# 3_30.net
KiCad netlist of a schematic drawn in EasyEDA Pro
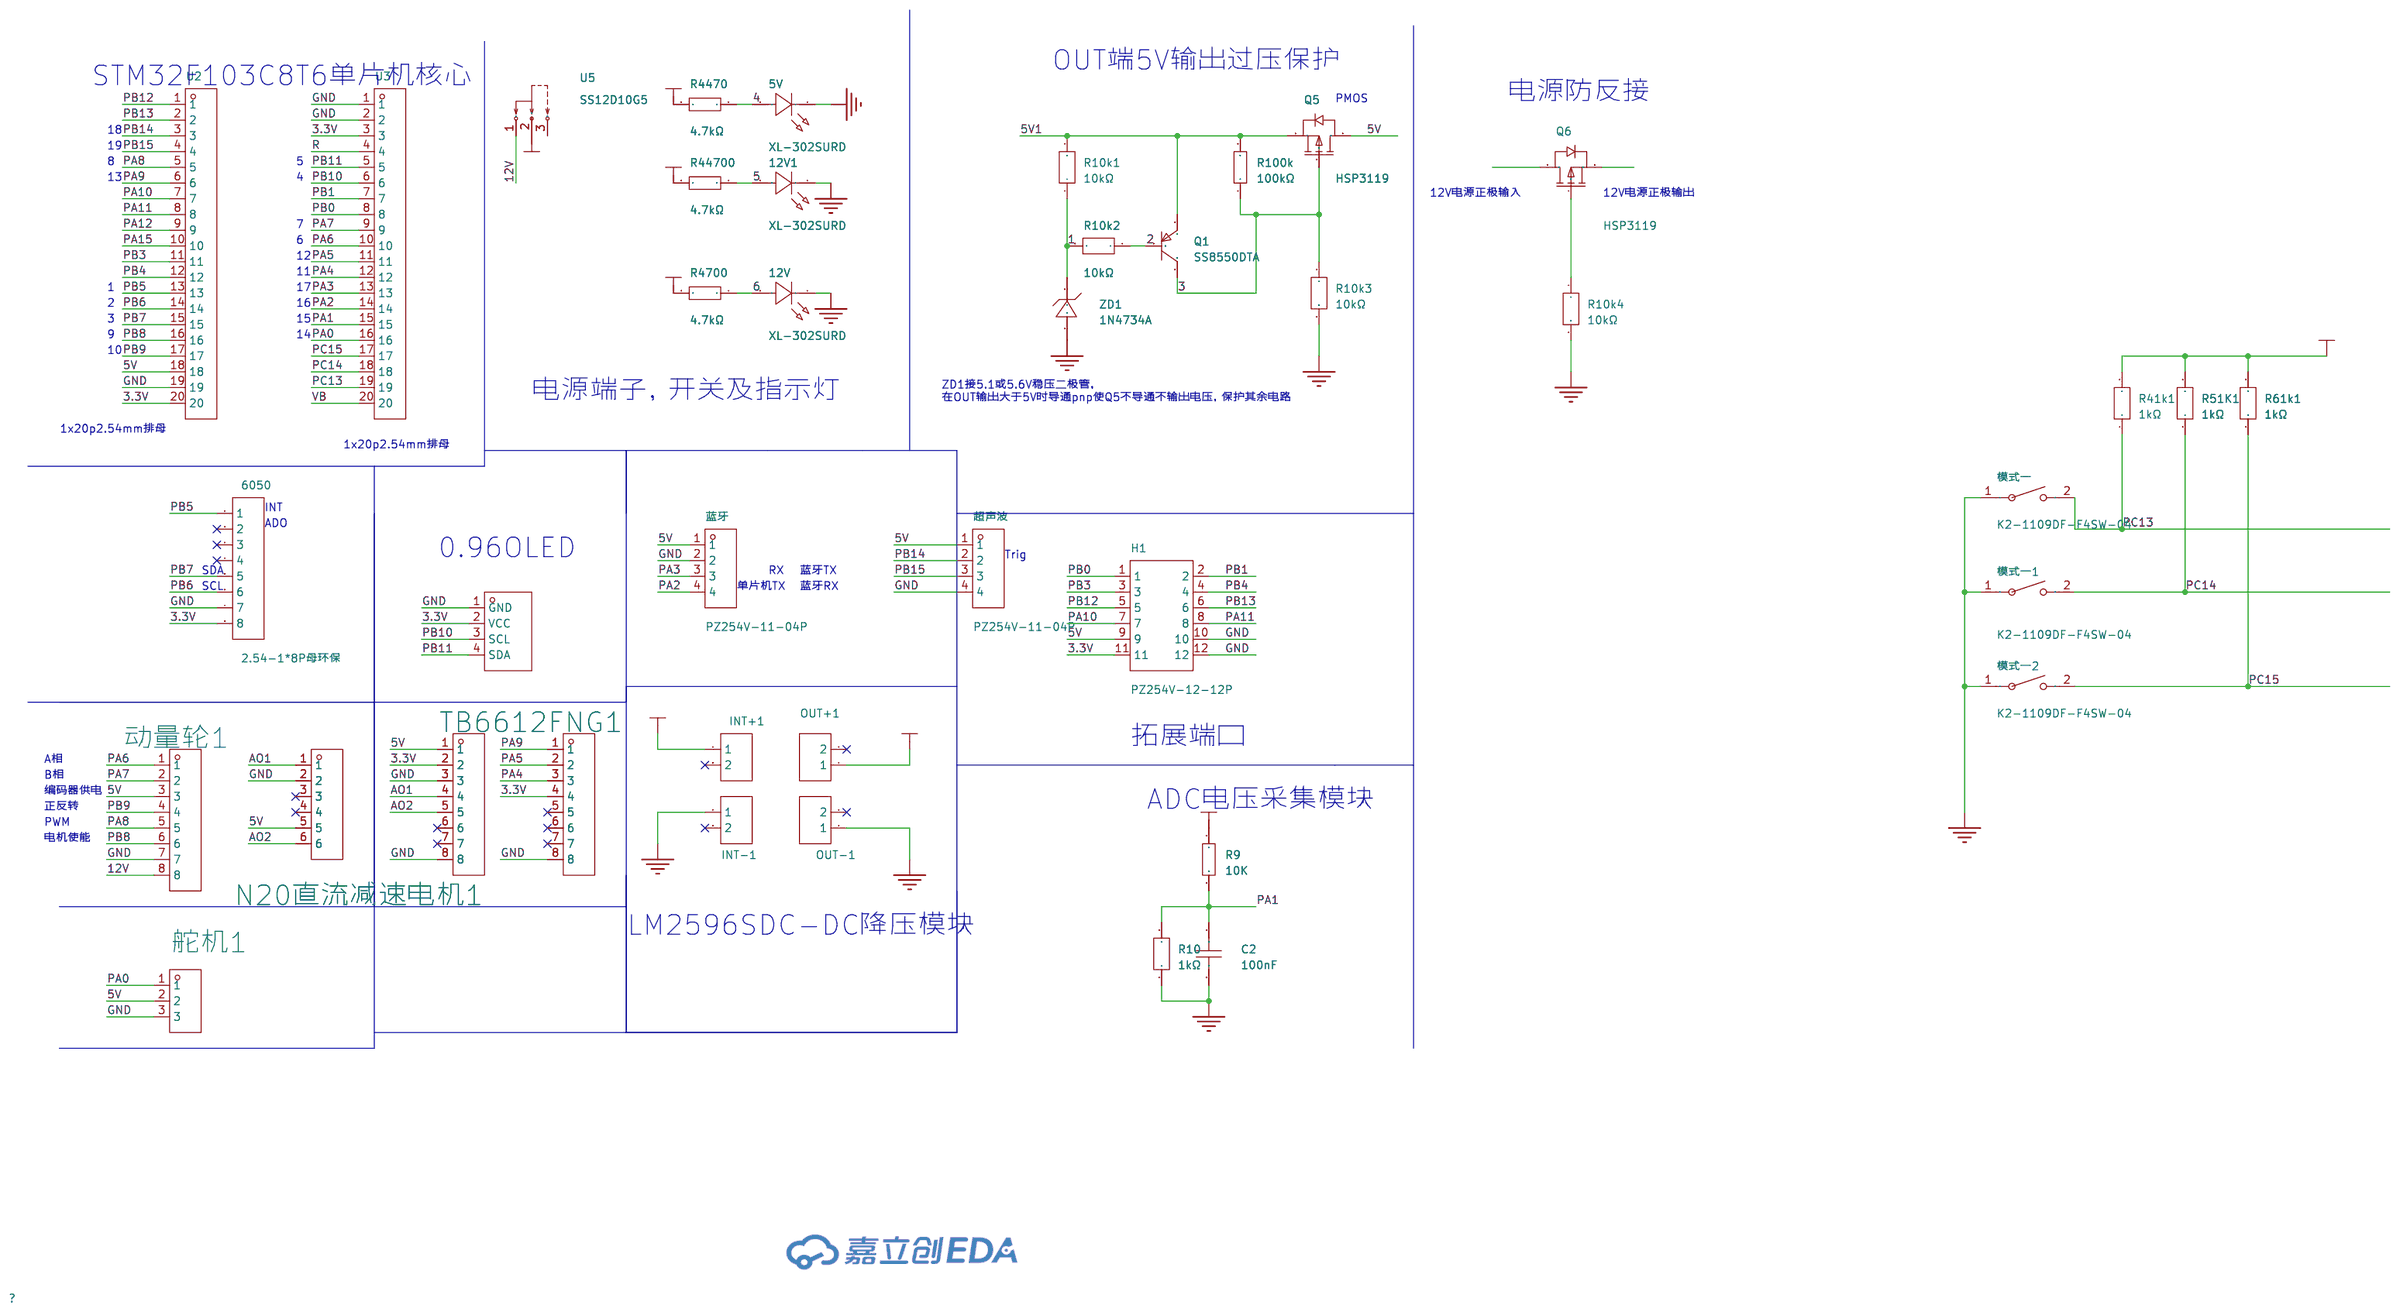
[diagram p0: schematic sheet]

(export (version "E")
  (design (tool "Eeschema 10.0.6"))
  (components
    (comp (ref "5V")
      (value "XL-302SURD")
      (footprint "easyedapro:LED-TH_BD3.8-P2.54-RD")
      (fields (field (name "Manufacturer") "XINGLIGHT(成兴光)"))
      (libsource (lib "easyedapro") (part "XL-302SURD"))
    )
    (comp (ref "12V")
      (value "XL-302SURD")
      (footprint "easyedapro:LED-TH_BD3.8-P2.54-RD")
      (fields (field (name "Manufacturer") "XINGLIGHT(成兴光)"))
      (libsource (lib "easyedapro") (part "XL-302SURD"))
    )
    (comp (ref "12V1")
      (value "XL-302SURD")
      (footprint "easyedapro:LED-TH_BD3.8-P2.54-RD")
      (fields (field (name "Manufacturer") "XINGLIGHT(成兴光)"))
      (libsource (lib "easyedapro") (part "XL-302SURD"))
    )
    (comp (ref "6050")
      (value "2.54-1*8P母环保")
      (footprint "easyedapro:HDR-TH_8P-P2.54-V-F-1")
      (description "插孔结构:1x8P;间距:2.54mm;行距:-;安装类型:直插;排数:单排;总孔位数:8P;塑高:-;触头材质:-;触头镀层:-;")
      (fields (field (name "Manufacturer") "BOOMELE(博穆精密)"))
      (libsource (lib "easyedapro") (part "Header-Female-2.54_1x8"))
    )
    (comp (ref "C2")
      (value "100nF")
      (footprint "easyedapro:C0603")
      (libsource (lib "easyedapro") (part "CapAcitance"))
    )
    (comp (ref "H1")
      (value "PZ254V-12-12P")
      (footprint "easyedapro:HDR-TH_12P-P2.54-V-M-R2-C6-S2.54")
      (fields (field (name "Manufacturer") "XFCN(兴飞)"))
      (libsource (lib "easyedapro") (part "PZ254V-12-12P"))
    )
    (comp (ref "INT+1")
      (value "2.54-1*2P母")
      (footprint "easyedapro:HDR-TH_2P-P2.54-V-F")
      (description "插孔结构:1x2P;间距:2.54mm;行距:-;安装类型:直插;排数:单排;总孔位数:2P;塑高:-;触头材质:-;触头镀层:-;")
      (fields (field (name "Manufacturer") "BOOMELE(博穆精密)"))
      (libsource (lib "easyedapro") (part "Header-Female-2.54_1x2"))
    )
    (comp (ref "INT-1")
      (value "2.54-1*2P母")
      (footprint "easyedapro:HDR-TH_2P-P2.54-V-F")
      (description "插孔结构:1x2P;间距:2.54mm;行距:-;安装类型:直插;排数:单排;总孔位数:2P;塑高:-;触头材质:-;触头镀层:-;")
      (fields (field (name "Manufacturer") "BOOMELE(博穆精密)"))
      (libsource (lib "easyedapro") (part "Header-Female-2.54_1x2"))
    )
    (comp (ref "N20直流减速电机1")
      (value "KH-2PH90-1X6P-L10.5")
      (footprint "easyedapro:HDR-TH_6P-P2.00-H-M-W7.2-N")
      (fields (field (name "Manufacturer") "kinghelm(金航标)"))
      (libsource (lib "easyedapro") (part "KH-2PH90-1X6P-L10.5"))
    )
    (comp (ref "OLED1")
      (value "HS96L03W2C03")
      (footprint "easyedapro:OLED-TH_L27.8-W27.2-P2.54_C9900033791")
      (description "主控芯片:SSD1315;接口类型:I2C;尺寸(inch):0.96;像素分辨率:128x64;")
      (fields (field (name "Manufacturer") "HS(汉昇)"))
      (libsource (lib "easyedapro") (part "HS96L03W2C03"))
    )
    (comp (ref "OUT+1")
      (value "2.54-1*2P母")
      (footprint "easyedapro:HDR-TH_2P-P2.54-V-F")
      (description "插孔结构:1x2P;间距:2.54mm;行距:-;安装类型:直插;排数:单排;总孔位数:2P;塑高:-;触头材质:-;触头镀层:-;")
      (fields (field (name "Manufacturer") "BOOMELE(博穆精密)"))
      (libsource (lib "easyedapro") (part "Header-Female-2.54_1x2"))
    )
    (comp (ref "OUT-1")
      (value "2.54-1*2P母")
      (footprint "easyedapro:HDR-TH_2P-P2.54-V-F")
      (description "插孔结构:1x2P;间距:2.54mm;行距:-;安装类型:直插;排数:单排;总孔位数:2P;塑高:-;触头材质:-;触头镀层:-;")
      (fields (field (name "Manufacturer") "BOOMELE(博穆精密)"))
      (libsource (lib "easyedapro") (part "Header-Female-2.54_1x2"))
    )
    (comp (ref "Q1")
      (value "SS8550DTA")
      (footprint "easyedapro:TO-92-3_L4.8-W3.7-P2.54-L")
      (description "晶体管类型:PNP;集电极电流(Ic):1.5A;集射极击穿电压(Vceo):25V;功率(Pd):2W;直流电流增益(hFE@Ic,Vce):40@800mA,1V;")
      (fields (field (name "Manufacturer") "onsemi(安森美)"))
      (libsource (lib "easyedapro") (part "SS8550DTA"))
    )
    (comp (ref "Q5")
      (value "HSP3119")
      (footprint "easyedapro:TO-220-3_L10.2-W4.5-P2.54-L-1")
      (description "类型:1个P沟道;漏源电压(Vdss):30V;连续漏极电流(Id):150A;导通电阻(RDS(on)):-;耗散功率(Pd):200W;阈值电压(Vgs(th)):2.5V;")
      (fields (field (name "Manufacturer") "HUASHUO(华朔)"))
      (libsource (lib "easyedapro") (part "HSP3119"))
    )
    (comp (ref "Q6")
      (value "HSP3119")
      (footprint "easyedapro:TO-220-3_L10.2-W4.5-P2.54-L-1")
      (description "类型:1个P沟道;漏源电压(Vdss):30V;连续漏极电流(Id):150A;导通电阻(RDS(on)):-;耗散功率(Pd):200W;阈值电压(Vgs(th)):2.5V;")
      (fields (field (name "Manufacturer") "HUASHUO(华朔)"))
      (libsource (lib "easyedapro") (part "HSP3119"))
    )
    (comp (ref "R9") (value "10K") (footprint "easyedapro:R0603") (libsource (lib "easyedapro") (part "电阻")))
    (comp (ref "R10")
      (value "1kΩ")
      (footprint "easyedapro:RES-TH_BD2.3-L6.5-P10.50-D0.5")
      (description "电阻类型:金属膜电阻;阻值:1kΩ;精度:±1%;功率:250mW;温度系数:±200ppm/°C;")
      (fields (field (name "Manufacturer Part") "MF1/4W-1KΩ±1%T52") (field (name "Manufacturer") "华星机电"))
      (libsource (lib "easyedapro") (part "MF1/4W-1KΩ±1%T52"))
    )
    (comp (ref "R10k1")
      (value "10kΩ")
      (footprint "easyedapro:RES-TH_BD2.4-L6.3-P10.30-D0.6")
      (description "电阻类型:金属膜电阻;阻值:10kΩ;精度:±1%;功率:250mW;温度系数:±50ppm/°C;")
      (fields
        (field (name "Manufacturer Part") "RN1/4W10KFT/BA1")
        (field (name "Manufacturer") "Tyohm(幸亚电阻)")
      )
      (libsource (lib "easyedapro") (part "RN 1/4W 10K F T/B A1"))
    )
    (comp (ref "R10k2")
      (value "10kΩ")
      (footprint "easyedapro:RES-TH_BD2.4-L6.3-P10.30-D0.6")
      (description "电阻类型:金属膜电阻;阻值:10kΩ;精度:±1%;功率:250mW;温度系数:±50ppm/°C;")
      (fields
        (field (name "Manufacturer Part") "RN1/4W10KFT/BA1")
        (field (name "Manufacturer") "Tyohm(幸亚电阻)")
      )
      (libsource (lib "easyedapro") (part "RN 1/4W 10K F T/B A1"))
    )
    (comp (ref "R10k3")
      (value "10kΩ")
      (footprint "easyedapro:RES-TH_BD2.4-L6.3-P10.30-D0.6")
      (description "电阻类型:金属膜电阻;阻值:10kΩ;精度:±1%;功率:250mW;温度系数:±50ppm/°C;")
      (fields
        (field (name "Manufacturer Part") "RN1/4W10KFT/BA1")
        (field (name "Manufacturer") "Tyohm(幸亚电阻)")
      )
      (libsource (lib "easyedapro") (part "RN 1/4W 10K F T/B A1"))
    )
    (comp (ref "R10k4")
      (value "10kΩ")
      (footprint "easyedapro:RES-TH_BD2.4-L6.3-P10.30-D0.6")
      (description "电阻类型:金属膜电阻;阻值:10kΩ;精度:±1%;功率:250mW;温度系数:±50ppm/°C;")
      (fields
        (field (name "Manufacturer Part") "RN1/4W10KFT/BA1")
        (field (name "Manufacturer") "Tyohm(幸亚电阻)")
      )
      (libsource (lib "easyedapro") (part "RN 1/4W 10K F T/B A1"))
    )
    (comp (ref "R41k1")
      (value "1kΩ")
      (footprint "easyedapro:RES-TH_BD2.3-L6.5-P10.50-D0.5")
      (description "电阻类型:金属膜电阻;阻值:1kΩ;精度:±1%;功率:250mW;温度系数:±200ppm/°C;")
      (fields (field (name "Manufacturer Part") "MF1/4W-1KΩ±1%T52") (field (name "Manufacturer") "华星机电"))
      (libsource (lib "easyedapro") (part "MF1/4W-1KΩ±1%T52"))
    )
    (comp (ref "R51K1")
      (value "1kΩ")
      (footprint "easyedapro:RES-TH_BD2.3-L6.5-P10.50-D0.5")
      (description "电阻类型:金属膜电阻;阻值:1kΩ;精度:±1%;功率:250mW;温度系数:±200ppm/°C;")
      (fields (field (name "Manufacturer Part") "MF1/4W-1KΩ±1%T52") (field (name "Manufacturer") "华星机电"))
      (libsource (lib "easyedapro") (part "MF1/4W-1KΩ±1%T52"))
    )
    (comp (ref "R61k1")
      (value "1kΩ")
      (footprint "easyedapro:RES-TH_BD2.3-L6.5-P10.50-D0.5")
      (description "电阻类型:金属膜电阻;阻值:1kΩ;精度:±1%;功率:250mW;温度系数:±200ppm/°C;")
      (fields (field (name "Manufacturer Part") "MF1/4W-1KΩ±1%T52") (field (name "Manufacturer") "华星机电"))
      (libsource (lib "easyedapro") (part "MF1/4W-1KΩ±1%T52"))
    )
    (comp (ref "R100k")
      (value "100kΩ")
      (footprint "easyedapro:RES-TH_BD2.7-L6.2-P10.20-D0.4")
      (description "电阻类型:金属膜电阻;阻值:100kΩ;精度:±1%;功率:250mW;温度系数:±350ppm/°C;")
      (fields (field (name "Manufacturer Part") "MF1/4W-100K±1%-OT26") (field (name "Manufacturer") "VO(翔胜)"))
      (libsource (lib "easyedapro") (part "MF1/4W-100K±1%-OT26"))
    )
    (comp (ref "R4470")
      (value "4.7kΩ")
      (footprint "easyedapro:R0402")
      (description "电阻类型:厚膜电阻;阻值:4.7kΩ;精度:±1%;功率:62.5mW;最大工作电压:50V;温度系数:±100ppm/°C;")
      (fields
        (field (name "Manufacturer Part") "0402WGF4701TCE")
        (field (name "Manufacturer") "UNI-ROYAL(厚声)")
      )
      (libsource (lib "easyedapro") (part "0402WGF4701TCE"))
    )
    (comp (ref "R4700")
      (value "4.7kΩ")
      (footprint "easyedapro:R0402")
      (description "电阻类型:厚膜电阻;阻值:4.7kΩ;精度:±1%;功率:62.5mW;最大工作电压:50V;温度系数:±100ppm/°C;")
      (fields
        (field (name "Manufacturer Part") "0402WGF4701TCE")
        (field (name "Manufacturer") "UNI-ROYAL(厚声)")
      )
      (libsource (lib "easyedapro") (part "0402WGF4701TCE"))
    )
    (comp (ref "R44700")
      (value "4.7kΩ")
      (footprint "easyedapro:R0402")
      (description "电阻类型:厚膜电阻;阻值:4.7kΩ;精度:±1%;功率:62.5mW;最大工作电压:50V;温度系数:±100ppm/°C;")
      (fields
        (field (name "Manufacturer Part") "0402WGF4701TCE")
        (field (name "Manufacturer") "UNI-ROYAL(厚声)")
      )
      (libsource (lib "easyedapro") (part "0402WGF4701TCE"))
    )
    (comp (ref "TB1")
      (value "2.54-1*8P/30mm(3+24+3)")
      (footprint "easyedapro:HDR-TH_8P-P2.54-V-M-4")
      (libsource (lib "easyedapro") (part "2.54-1*8P/30MM(3+24+3)"))
    )
    (comp (ref "TB6612FNG1")
      (value "2.54-1*8P/30mm(3+24+3)")
      (footprint "easyedapro:HDR-TH_8P-P2.54-V-M-4")
      (libsource (lib "easyedapro") (part "2.54-1*8P/30MM(3+24+3)"))
    )
    (comp (ref "U2")
      (value "KH-2FH-1X20P-H4.3")
      (footprint "easyedapro:HDR-TH_20P-P2.00-V-F-A")
      (fields (field (name "Manufacturer") "kinghelm(金航标)"))
      (libsource (lib "easyedapro") (part "KH-2FH-1X20P-H4.3"))
    )
    (comp (ref "U3")
      (value "KH-2FH-1X20P-H4.3")
      (footprint "easyedapro:HDR-TH_20P-P2.00-V-F-A")
      (fields (field (name "Manufacturer") "kinghelm(金航标)"))
      (libsource (lib "easyedapro") (part "KH-2FH-1X20P-H4.3"))
    )
    (comp (ref "U5")
      (value "SS12D10G5")
      (footprint "easyedapro:SW-TH_SHOU-HAN_SS12D10G4")
      (description "电路结构:单刀双掷;安装方式:直插;额定电流(DC):2A;额定电压(DC):125V;机械寿命:3千次;")
      (fields (field (name "Manufacturer") "SHOU HAN(首韩)"))
      (libsource (lib "easyedapro") (part "SS12D10G5"))
    )
    (comp (ref "ZD1")
      (value "1N4734A")
      (footprint "easyedapro:DO-41_BD2.8-L4.2-P8.00-D0.7-FD")
      (description "二极管配置:独立式;稳压值(标称值):5.6V;耗散功率(Pd):-;")
      (fields (field (name "Manufacturer") "ST(先科)"))
      (libsource (lib "easyedapro") (part "1N4734A_C41430"))
    )
    (comp (ref "动量轮1")
      (value "2.54-1*8P/30mm(3+24+3)")
      (footprint "easyedapro:HDR-TH_8P-P2.54-V-M-4")
      (libsource (lib "easyedapro") (part "2.54-1*8P/30MM(3+24+3)"))
    )
    (comp (ref "模式一")
      (value "K2-1109DF-F4SW-04")
      (footprint "easyedapro:SW-TH_HRO_K2-1109DF-FXXW-XX")
      (description "4.5*4.5*6两脚侧按开关")
      (fields (field (name "Manufacturer") "韩国韩荣"))
      (libsource (lib "easyedapro") (part "K2-1109DF-F4SW-04"))
    )
    (comp (ref "模式一1")
      (value "K2-1109DF-F4SW-04")
      (footprint "easyedapro:SW-TH_HRO_K2-1109DF-FXXW-XX")
      (description "4.5*4.5*6两脚侧按开关")
      (fields (field (name "Manufacturer") "韩国韩荣"))
      (libsource (lib "easyedapro") (part "K2-1109DF-F4SW-04"))
    )
    (comp (ref "模式一2")
      (value "K2-1109DF-F4SW-04")
      (footprint "easyedapro:SW-TH_HRO_K2-1109DF-FXXW-XX")
      (description "4.5*4.5*6两脚侧按开关")
      (fields (field (name "Manufacturer") "韩国韩荣"))
      (libsource (lib "easyedapro") (part "K2-1109DF-F4SW-04"))
    )
    (comp (ref "舵机1")
      (value "PM254V-11-03-H85")
      (footprint "easyedapro:HDR-TH_3P-P2.54-V-F")
      (description "插孔结构:1x3P;间距:2.54mm;行距:-;安装类型:直插;排数:单排;总孔位数:3P;塑高:-;触头材质:黄铜;触头镀层:-;")
      (fields (field (name "Manufacturer") "XFCN(兴飞)"))
      (libsource (lib "easyedapro") (part "PM254V-11-03-H85"))
    )
    (comp (ref "蓝牙")
      (value "PZ254V-11-04P")
      (footprint "easyedapro:HDR-TH_4P-P2.54-V-M")
      (fields (field (name "Manufacturer") "XFCN(兴飞)"))
      (libsource (lib "easyedapro") (part "PZ254V-11-04P_C2691448"))
    )
    (comp (ref "超声波")
      (value "PZ254V-11-04P")
      (footprint "easyedapro:HDR-TH_4P-P2.54-V-M")
      (fields (field (name "Manufacturer") "XFCN(兴飞)"))
      (libsource (lib "easyedapro") (part "PZ254V-11-04P_C2691448"))
    )
  )
  (nets
    (net (code "1") (name "/1") (class "Default")
      (node (ref "R10k1") (pin "1") (pinfunction "1_1") (pintype "unspecified"))
      (node (ref "R10k2") (pin "2") (pinfunction "2_2") (pintype "unspecified"))
      (node (ref "ZD1") (pin "2") (pinfunction "K_2") (pintype "unspecified"))
    )
    (net (code "2") (name "/2") (class "Default")
      (node (ref "Q1") (pin "2") (pinfunction "B_2") (pintype "unspecified"))
      (node (ref "R10k2") (pin "1") (pinfunction "1_1") (pintype "unspecified"))
    )
    (net (code "3") (name "/3") (class "Default")
      (node (ref "Q1") (pin "3") (pinfunction "C_3") (pintype "unspecified"))
      (node (ref "Q5") (pin "1") (pinfunction "G_1") (pintype "unspecified"))
      (node (ref "R100k") (pin "1") (pinfunction "1_1") (pintype "unspecified"))
      (node (ref "R10k3") (pin "1") (pinfunction "1_1") (pintype "unspecified"))
    )
    (net (code "4") (name "/4") (class "Default")
      (node (ref "5V") (pin "2") (pinfunction "A_2") (pintype "unspecified"))
      (node (ref "R4470") (pin "1") (pinfunction "1_1") (pintype "input"))
    )
    (net (code "5") (name "/5") (class "Default")
      (node (ref "12V1") (pin "2") (pinfunction "A_2") (pintype "unspecified"))
      (node (ref "R44700") (pin "1") (pinfunction "1_1") (pintype "input"))
    )
    (net (code "6") (name "/6") (class "Default")
      (node (ref "12V") (pin "2") (pinfunction "A_2") (pintype "unspecified"))
      (node (ref "R4700") (pin "1") (pinfunction "1_1") (pintype "input"))
    )
    (net (code "7") (name "/AO1") (class "Default")
      (node (ref "N20直流减速电机1") (pin "1") (pinfunction "1_1") (pintype "unspecified"))
      (node (ref "TB6612FNG1") (pin "4") (pinfunction "4_4") (pintype "unspecified"))
    )
    (net (code "8") (name "/AO2") (class "Default")
      (node (ref "N20直流减速电机1") (pin "6") (pinfunction "6_6") (pintype "unspecified"))
      (node (ref "TB6612FNG1") (pin "5") (pinfunction "5_5") (pintype "unspecified"))
    )
    (net (code "9") (name "/PA0") (class "Default")
      (node (ref "U3") (pin "16") (pinfunction "16_16") (pintype "unspecified"))
      (node (ref "舵机1") (pin "1") (pinfunction "1_1") (pintype "unspecified"))
    )
    (net (code "10") (name "/PA1") (class "Default")
      (node (ref "C2") (pin "2") (pinfunction "2_2") (pintype "input"))
      (node (ref "R10") (pin "2") (pinfunction "2_2") (pintype "unspecified"))
      (node (ref "R9") (pin "1") (pinfunction "1_1") (pintype "input"))
      (node (ref "U3") (pin "15") (pinfunction "15_15") (pintype "unspecified"))
    )
    (net (code "11") (name "/PA2") (class "Default")
      (node (ref "U3") (pin "14") (pinfunction "14_14") (pintype "unspecified"))
      (node (ref "蓝牙") (pin "4") (pinfunction "4_4") (pintype "unspecified"))
    )
    (net (code "12") (name "/PA3") (class "Default")
      (node (ref "U3") (pin "13") (pinfunction "13_13") (pintype "unspecified"))
      (node (ref "蓝牙") (pin "3") (pinfunction "3_3") (pintype "unspecified"))
    )
    (net (code "13") (name "/PA4") (class "Default")
      (node (ref "TB1") (pin "3") (pinfunction "3_3") (pintype "unspecified"))
      (node (ref "U3") (pin "12") (pinfunction "12_12") (pintype "unspecified"))
    )
    (net (code "14") (name "/PA5") (class "Default")
      (node (ref "TB1") (pin "2") (pinfunction "2_2") (pintype "unspecified"))
      (node (ref "U3") (pin "11") (pinfunction "11_11") (pintype "unspecified"))
    )
    (net (code "15") (name "/PA6") (class "Default")
      (node (ref "U3") (pin "10") (pinfunction "10_10") (pintype "unspecified"))
      (node (ref "动量轮1") (pin "1") (pinfunction "1_1") (pintype "unspecified"))
    )
    (net (code "16") (name "/PA7") (class "Default")
      (node (ref "U3") (pin "9") (pinfunction "9_9") (pintype "unspecified"))
      (node (ref "动量轮1") (pin "2") (pinfunction "2_2") (pintype "unspecified"))
    )
    (net (code "17") (name "/PA8") (class "Default")
      (node (ref "U2") (pin "5") (pinfunction "5_5") (pintype "unspecified"))
      (node (ref "动量轮1") (pin "5") (pinfunction "5_5") (pintype "unspecified"))
    )
    (net (code "18") (name "/PA9") (class "Default")
      (node (ref "TB1") (pin "1") (pinfunction "1_1") (pintype "unspecified"))
      (node (ref "U2") (pin "6") (pinfunction "6_6") (pintype "unspecified"))
    )
    (net (code "19") (name "/PA10") (class "Default")
      (node (ref "H1") (pin "7") (pinfunction "7_7") (pintype "unspecified"))
      (node (ref "U2") (pin "7") (pinfunction "7_7") (pintype "unspecified"))
    )
    (net (code "20") (name "/PA11") (class "Default")
      (node (ref "H1") (pin "8") (pinfunction "8_8") (pintype "unspecified"))
      (node (ref "U2") (pin "8") (pinfunction "8_8") (pintype "unspecified"))
    )
    (net (code "21") (name "/PA12") (class "Default")
      (node (ref "U2") (pin "9") (pinfunction "9_9") (pintype "unspecified"))
    )
    (net (code "22") (name "/PA15") (class "Default")
      (node (ref "U2") (pin "10") (pinfunction "10_10") (pintype "unspecified"))
    )
    (net (code "23") (name "/PB0") (class "Default")
      (node (ref "H1") (pin "1") (pinfunction "1_1") (pintype "unspecified"))
      (node (ref "U3") (pin "8") (pinfunction "8_8") (pintype "unspecified"))
    )
    (net (code "24") (name "/PB1") (class "Default")
      (node (ref "H1") (pin "2") (pinfunction "2_2") (pintype "unspecified"))
      (node (ref "U3") (pin "7") (pinfunction "7_7") (pintype "unspecified"))
    )
    (net (code "25") (name "/PB3") (class "Default")
      (node (ref "H1") (pin "3") (pinfunction "3_3") (pintype "unspecified"))
      (node (ref "U2") (pin "11") (pinfunction "11_11") (pintype "unspecified"))
    )
    (net (code "26") (name "/PB4") (class "Default")
      (node (ref "H1") (pin "4") (pinfunction "4_4") (pintype "unspecified"))
      (node (ref "U2") (pin "12") (pinfunction "12_12") (pintype "unspecified"))
    )
    (net (code "27") (name "/PB5") (class "Default")
      (node (ref "6050") (pin "1") (pinfunction "1_1") (pintype "input"))
      (node (ref "U2") (pin "13") (pinfunction "13_13") (pintype "unspecified"))
    )
    (net (code "28") (name "/PB6") (class "Default")
      (node (ref "6050") (pin "6") (pinfunction "6_6") (pintype "input"))
      (node (ref "U2") (pin "14") (pinfunction "14_14") (pintype "unspecified"))
    )
    (net (code "29") (name "/PB7") (class "Default")
      (node (ref "6050") (pin "5") (pinfunction "5_5") (pintype "input"))
      (node (ref "U2") (pin "15") (pinfunction "15_15") (pintype "unspecified"))
    )
    (net (code "30") (name "/PB8") (class "Default")
      (node (ref "U2") (pin "16") (pinfunction "16_16") (pintype "unspecified"))
      (node (ref "动量轮1") (pin "6") (pinfunction "6_6") (pintype "unspecified"))
    )
    (net (code "31") (name "/PB9") (class "Default")
      (node (ref "U2") (pin "17") (pinfunction "17_17") (pintype "unspecified"))
      (node (ref "动量轮1") (pin "4") (pinfunction "4_4") (pintype "unspecified"))
    )
    (net (code "32") (name "/PB10") (class "Default")
      (node (ref "OLED1") (pin "3") (pinfunction "SCL_3") (pintype "unspecified"))
      (node (ref "U3") (pin "6") (pinfunction "6_6") (pintype "unspecified"))
    )
    (net (code "33") (name "/PB11") (class "Default")
      (node (ref "OLED1") (pin "4") (pinfunction "SDA_4") (pintype "unspecified"))
      (node (ref "U3") (pin "5") (pinfunction "5_5") (pintype "unspecified"))
    )
    (net (code "34") (name "/PB12") (class "Default")
      (node (ref "H1") (pin "5") (pinfunction "5_5") (pintype "unspecified"))
      (node (ref "U2") (pin "1") (pinfunction "1_1") (pintype "unspecified"))
    )
    (net (code "35") (name "/PB13") (class "Default")
      (node (ref "H1") (pin "6") (pinfunction "6_6") (pintype "unspecified"))
      (node (ref "U2") (pin "2") (pinfunction "2_2") (pintype "unspecified"))
    )
    (net (code "36") (name "/PB14") (class "Default")
      (node (ref "U2") (pin "3") (pinfunction "3_3") (pintype "unspecified"))
      (node (ref "超声波") (pin "2") (pinfunction "2_2") (pintype "unspecified"))
    )
    (net (code "37") (name "/PB15") (class "Default")
      (node (ref "U2") (pin "4") (pinfunction "4_4") (pintype "unspecified"))
      (node (ref "超声波") (pin "3") (pinfunction "3_3") (pintype "unspecified"))
    )
    (net (code "38") (name "/PC13") (class "Default")
      (node (ref "R41k1") (pin "1") (pinfunction "1_1") (pintype "unspecified"))
      (node (ref "U3") (pin "19") (pinfunction "19_19") (pintype "unspecified"))
      (node (ref "模式一") (pin "2") (pinfunction "2_2") (pintype "unspecified"))
    )
    (net (code "39") (name "/PC14") (class "Default")
      (node (ref "R51K1") (pin "1") (pinfunction "1_1") (pintype "unspecified"))
      (node (ref "U3") (pin "18") (pinfunction "18_18") (pintype "unspecified"))
      (node (ref "模式一1") (pin "2") (pinfunction "2_2") (pintype "unspecified"))
    )
    (net (code "40") (name "/PC15") (class "Default")
      (node (ref "R61k1") (pin "1") (pinfunction "1_1") (pintype "unspecified"))
      (node (ref "U3") (pin "17") (pinfunction "17_17") (pintype "unspecified"))
      (node (ref "模式一2") (pin "2") (pinfunction "2_2") (pintype "unspecified"))
    )
    (net (code "41") (name "/R") (class "Default")
      (node (ref "U3") (pin "4") (pinfunction "4_4") (pintype "unspecified"))
    )
    (net (code "42") (name "/VB") (class "Default")
      (node (ref "U3") (pin "20") (pinfunction "20_20") (pintype "unspecified"))
    )
    (net (code "43") (name "3.3V") (class "Default")
      (node (ref "6050") (pin "8") (pinfunction "8_8") (pintype "input"))
      (node (ref "H1") (pin "11") (pinfunction "11_11") (pintype "unspecified"))
      (node (ref "OLED1") (pin "2") (pinfunction "VCC_2") (pintype "unspecified"))
      (node (ref "R41k1") (pin "2") (pinfunction "2_2") (pintype "unspecified"))
      (node (ref "R51K1") (pin "2") (pinfunction "2_2") (pintype "unspecified"))
      (node (ref "R61k1") (pin "2") (pinfunction "2_2") (pintype "unspecified"))
      (node (ref "TB1") (pin "4") (pinfunction "4_4") (pintype "unspecified"))
      (node (ref "TB6612FNG1") (pin "2") (pinfunction "2_2") (pintype "unspecified"))
      (node (ref "U2") (pin "20") (pinfunction "20_20") (pintype "unspecified"))
      (node (ref "U3") (pin "3") (pinfunction "3_3") (pintype "unspecified"))
    )
    (net (code "44") (name "5V") (class "Default")
      (node (ref "H1") (pin "9") (pinfunction "9_9") (pintype "unspecified"))
      (node (ref "N20直流减速电机1") (pin "5") (pinfunction "5_5") (pintype "unspecified"))
      (node (ref "Q5") (pin "2") (pinfunction "D_2") (pintype "unspecified"))
      (node (ref "R4470") (pin "2") (pinfunction "2_2") (pintype "input"))
      (node (ref "TB6612FNG1") (pin "1") (pinfunction "1_1") (pintype "unspecified"))
      (node (ref "U2") (pin "18") (pinfunction "18_18") (pintype "unspecified"))
      (node (ref "动量轮1") (pin "3") (pinfunction "3_3") (pintype "unspecified"))
      (node (ref "舵机1") (pin "2") (pinfunction "2_2") (pintype "unspecified"))
      (node (ref "蓝牙") (pin "1") (pinfunction "1_1") (pintype "unspecified"))
      (node (ref "超声波") (pin "1") (pinfunction "1_1") (pintype "unspecified"))
    )
    (net (code "45") (name "5V1") (class "Default")
      (node (ref "OUT+1") (pin "1") (pinfunction "1_1") (pintype "input"))
      (node (ref "Q1") (pin "1") (pinfunction "E_1") (pintype "unspecified"))
      (node (ref "Q5") (pin "3") (pinfunction "S_3") (pintype "unspecified"))
      (node (ref "R100k") (pin "2") (pinfunction "2_2") (pintype "unspecified"))
      (node (ref "R10k1") (pin "2") (pinfunction "2_2") (pintype "unspecified"))
    )
    (net (code "46") (name "12V") (class "Default")
      (node (ref "INT+1") (pin "1") (pinfunction "1_1") (pintype "input"))
      (node (ref "R4700") (pin "2") (pinfunction "2_2") (pintype "input"))
      (node (ref "R9") (pin "2") (pinfunction "2_2") (pintype "input"))
      (node (ref "U5") (pin "1") (pinfunction "1_1") (pintype "unspecified"))
      (node (ref "动量轮1") (pin "8") (pinfunction "8_8") (pintype "unspecified"))
    )
    (net (code "47") (name "12V1") (class "Default")
      (node (ref "R44700") (pin "2") (pinfunction "2_2") (pintype "input"))
      (node (ref "U5") (pin "2") (pinfunction "2_2") (pintype "unspecified"))
    )
    (net (code "48") (name "GND") (class "Default")
      (node (ref "12V") (pin "1") (pinfunction "K_1") (pintype "unspecified"))
      (node (ref "12V1") (pin "1") (pinfunction "K_1") (pintype "unspecified"))
      (node (ref "5V") (pin "1") (pinfunction "K_1") (pintype "unspecified"))
      (node (ref "6050") (pin "7") (pinfunction "7_7") (pintype "input"))
      (node (ref "C2") (pin "1") (pinfunction "1_1") (pintype "input"))
      (node (ref "H1") (pin "10") (pinfunction "10_10") (pintype "unspecified"))
      (node (ref "H1") (pin "12") (pinfunction "12_12") (pintype "unspecified"))
      (node (ref "INT-1") (pin "1") (pinfunction "1_1") (pintype "input"))
      (node (ref "N20直流减速电机1") (pin "2") (pinfunction "2_2") (pintype "unspecified"))
      (node (ref "OLED1") (pin "1") (pinfunction "GND_1") (pintype "unspecified"))
      (node (ref "OUT-1") (pin "1") (pinfunction "1_1") (pintype "input"))
      (node (ref "R10") (pin "1") (pinfunction "1_1") (pintype "unspecified"))
      (node (ref "R10k3") (pin "2") (pinfunction "2_2") (pintype "unspecified"))
      (node (ref "R10k4") (pin "2") (pinfunction "2_2") (pintype "unspecified"))
      (node (ref "TB1") (pin "8") (pinfunction "8_8") (pintype "unspecified"))
      (node (ref "TB6612FNG1") (pin "3") (pinfunction "3_3") (pintype "unspecified"))
      (node (ref "TB6612FNG1") (pin "8") (pinfunction "8_8") (pintype "unspecified"))
      (node (ref "U2") (pin "19") (pinfunction "19_19") (pintype "unspecified"))
      (node (ref "U3") (pin "1") (pinfunction "1_1") (pintype "unspecified"))
      (node (ref "U3") (pin "2") (pinfunction "2_2") (pintype "unspecified"))
      (node (ref "ZD1") (pin "1") (pinfunction "A_1") (pintype "unspecified"))
      (node (ref "动量轮1") (pin "7") (pinfunction "7_7") (pintype "unspecified"))
      (node (ref "模式一") (pin "1") (pinfunction "1_1") (pintype "unspecified"))
      (node (ref "模式一1") (pin "1") (pinfunction "1_1") (pintype "unspecified"))
      (node (ref "模式一2") (pin "1") (pinfunction "1_1") (pintype "unspecified"))
      (node (ref "舵机1") (pin "3") (pinfunction "3_3") (pintype "unspecified"))
      (node (ref "蓝牙") (pin "2") (pinfunction "2_2") (pintype "unspecified"))
      (node (ref "超声波") (pin "4") (pinfunction "4_4") (pintype "unspecified"))
    )
    (net (code "49") (name "Net-(Q6-G)") (class "Default")
      (node (ref "Q6") (pin "1") (pinfunction "G_1") (pintype "unspecified"))
      (node (ref "R10k4") (pin "1") (pinfunction "1_1") (pintype "unspecified"))
    )
    (net (code "50") (name "unconnected-(6050-Pad2)") (class "Default")
      (node (ref "6050") (pin "2") (pinfunction "2_2") (pintype "input+no_connect"))
    )
    (net (code "51") (name "unconnected-(6050-Pad3)") (class "Default")
      (node (ref "6050") (pin "3") (pinfunction "3_3") (pintype "input+no_connect"))
    )
    (net (code "52") (name "unconnected-(6050-Pad4)") (class "Default")
      (node (ref "6050") (pin "4") (pinfunction "4_4") (pintype "input+no_connect"))
    )
    (net (code "53") (name "unconnected-(INT+1-Pad2)") (class "Default")
      (node (ref "INT+1") (pin "2") (pinfunction "2_2") (pintype "input+no_connect"))
    )
    (net (code "54") (name "unconnected-(INT-1-Pad2)") (class "Default")
      (node (ref "INT-1") (pin "2") (pinfunction "2_2") (pintype "input+no_connect"))
    )
    (net (code "55") (name "unconnected-(N20直流减速电机1-Pad3)") (class "Default")
      (node (ref "N20直流减速电机1") (pin "3") (pinfunction "3_3") (pintype "unspecified+no_connect"))
    )
    (net (code "56") (name "unconnected-(N20直流减速电机1-Pad4)") (class "Default")
      (node (ref "N20直流减速电机1") (pin "4") (pinfunction "4_4") (pintype "unspecified+no_connect"))
    )
    (net (code "57") (name "unconnected-(OUT+1-Pad2)") (class "Default")
      (node (ref "OUT+1") (pin "2") (pinfunction "2_2") (pintype "input+no_connect"))
    )
    (net (code "58") (name "unconnected-(OUT-1-Pad2)") (class "Default")
      (node (ref "OUT-1") (pin "2") (pinfunction "2_2") (pintype "input+no_connect"))
    )
    (net (code "59") (name "unconnected-(Q6-D-Pad2)") (class "Default")
      (node (ref "Q6") (pin "2") (pinfunction "D_2") (pintype "unspecified"))
    )
    (net (code "60") (name "unconnected-(Q6-S-Pad3)") (class "Default")
      (node (ref "Q6") (pin "3") (pinfunction "S_3") (pintype "unspecified"))
    )
    (net (code "61") (name "unconnected-(TB1-Pad5)") (class "Default")
      (node (ref "TB1") (pin "5") (pinfunction "5_5") (pintype "unspecified+no_connect"))
    )
    (net (code "62") (name "unconnected-(TB1-Pad6)") (class "Default")
      (node (ref "TB1") (pin "6") (pinfunction "6_6") (pintype "unspecified+no_connect"))
    )
    (net (code "63") (name "unconnected-(TB1-Pad7)") (class "Default")
      (node (ref "TB1") (pin "7") (pinfunction "7_7") (pintype "unspecified+no_connect"))
    )
    (net (code "64") (name "unconnected-(TB6612FNG1-Pad6)") (class "Default")
      (node (ref "TB6612FNG1") (pin "6") (pinfunction "6_6") (pintype "unspecified+no_connect"))
    )
    (net (code "65") (name "unconnected-(TB6612FNG1-Pad7)") (class "Default")
      (node (ref "TB6612FNG1") (pin "7") (pinfunction "7_7") (pintype "unspecified+no_connect"))
    )
    (net (code "66") (name "unconnected-(U5-Pad3)") (class "Default")
      (node (ref "U5") (pin "3") (pinfunction "3_3") (pintype "unspecified"))
    )
  )
)
